# guac_v1.net
KiCad netlist of a schematic drawn in EAGLE
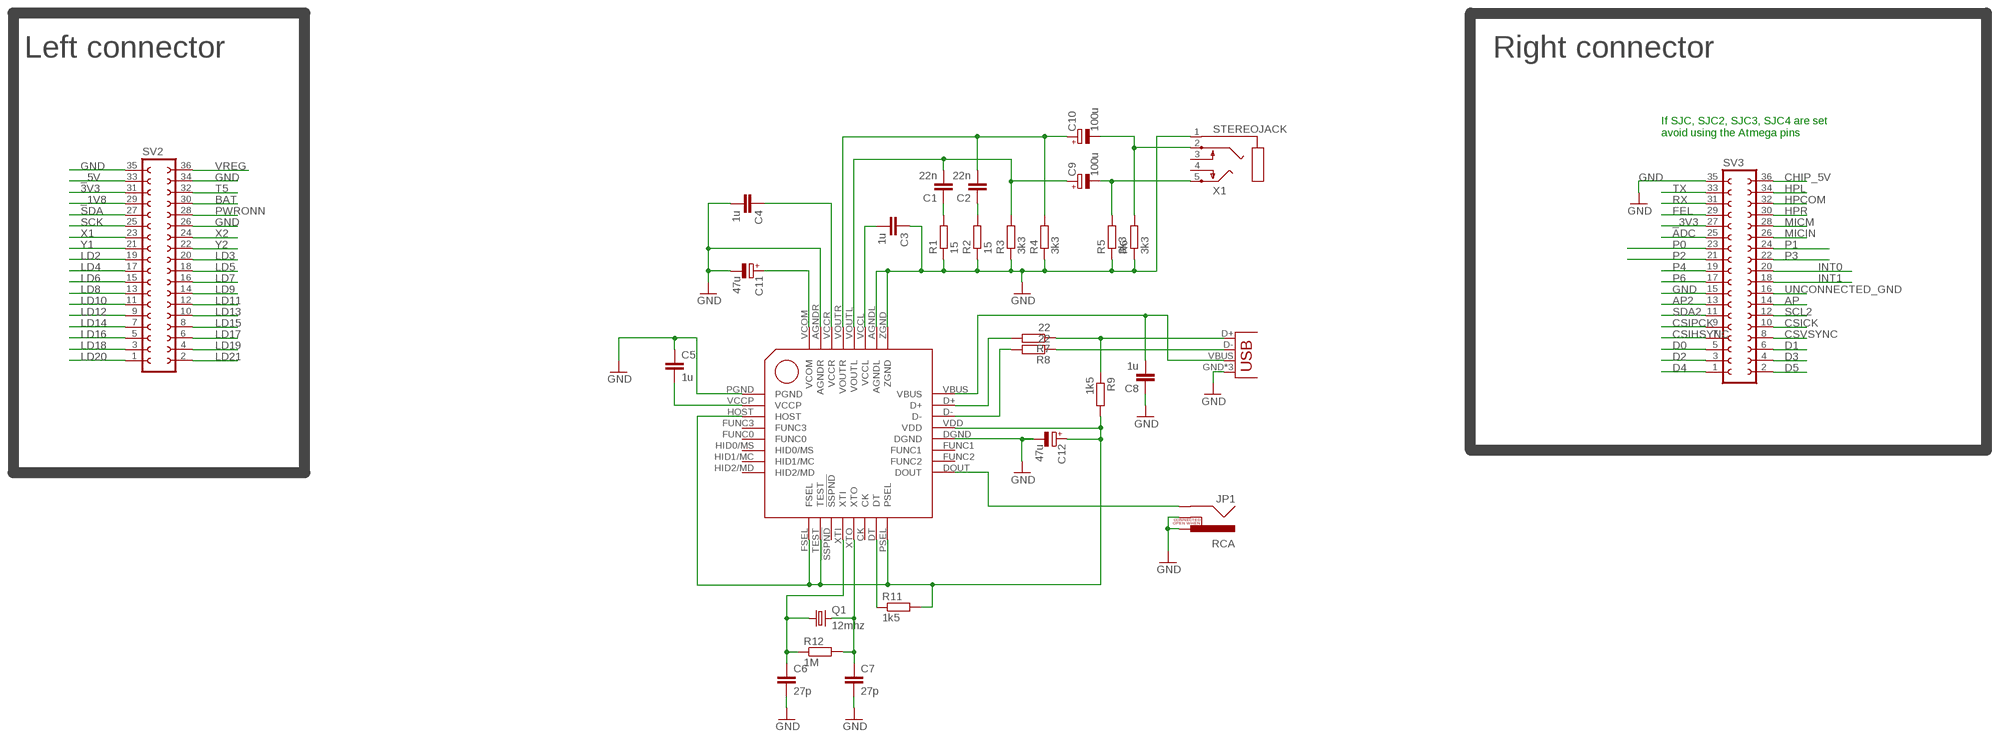
[diagram p0: schematic, sheet 1]

(export (version "E")
  (design (tool "Eeschema 10.0.6"))
  (components
    (comp (ref "C1")
      (value "22n")
      (footprint "eagle-import:C0805")
      (libsource (lib "eagle-import") (part "C-EUC0805"))
    )
    (comp (ref "C2")
      (value "22n")
      (footprint "eagle-import:C0805")
      (libsource (lib "eagle-import") (part "C-EUC0805"))
    )
    (comp (ref "C3")
      (value "1u")
      (footprint "eagle-import:C0805")
      (libsource (lib "eagle-import") (part "C-EUC0805"))
    )
    (comp (ref "C4")
      (value "1u")
      (footprint "eagle-import:C0805")
      (libsource (lib "eagle-import") (part "C-EUC0805"))
    )
    (comp (ref "C5")
      (value "1u")
      (footprint "eagle-import:C0805")
      (libsource (lib "eagle-import") (part "C-EUC0805"))
    )
    (comp (ref "C6")
      (value "27p")
      (footprint "eagle-import:C0805")
      (libsource (lib "eagle-import") (part "C-EUC0805"))
    )
    (comp (ref "C7")
      (value "27p")
      (footprint "eagle-import:C0805")
      (libsource (lib "eagle-import") (part "C-EUC0805"))
    )
    (comp (ref "C8")
      (value "1u")
      (footprint "eagle-import:C0805")
      (libsource (lib "eagle-import") (part "C-EUC0805"))
    )
    (comp (ref "C9")
      (value "100u")
      (footprint "eagle-import:140CLH-0810")
      (libsource (lib "eagle-import") (part "CPOL-EU140CLH-0810"))
    )
    (comp (ref "C10")
      (value "100u")
      (footprint "eagle-import:140CLH-0810")
      (libsource (lib "eagle-import") (part "CPOL-EU140CLH-0810"))
    )
    (comp (ref "C11")
      (value "47u")
      (footprint "eagle-import:140CLH-0810")
      (libsource (lib "eagle-import") (part "CPOL-EU140CLH-0810"))
    )
    (comp (ref "C12")
      (value "47u")
      (footprint "eagle-import:140CLH-0810")
      (libsource (lib "eagle-import") (part "CPOL-EU140CLH-0810"))
    )
    (comp (ref "JP1")
      (value "RCA")
      (footprint "eagle-import:RCA")
      (libsource (lib "eagle-import") (part "RCA"))
    )
    (comp (ref "Q1")
      (value "12mhz")
      (footprint "eagle-import:HC49UP")
      (libsource (lib "eagle-import") (part "CRYSTALHC49UP"))
    )
    (comp (ref "R1")
      (value "15")
      (footprint "eagle-import:M0805")
      (libsource (lib "eagle-import") (part "R-EU_M0805"))
    )
    (comp (ref "R2")
      (value "15")
      (footprint "eagle-import:M0805")
      (libsource (lib "eagle-import") (part "R-EU_M0805"))
    )
    (comp (ref "R3")
      (value "3k3")
      (footprint "eagle-import:M0805")
      (libsource (lib "eagle-import") (part "R-EU_M0805"))
    )
    (comp (ref "R4")
      (value "3k3")
      (footprint "eagle-import:M0805")
      (libsource (lib "eagle-import") (part "R-EU_M0805"))
    )
    (comp (ref "R5")
      (value "3k3")
      (footprint "eagle-import:M0805")
      (libsource (lib "eagle-import") (part "R-EU_M0805"))
    )
    (comp (ref "R6")
      (value "3k3")
      (footprint "eagle-import:M0805")
      (libsource (lib "eagle-import") (part "R-EU_M0805"))
    )
    (comp (ref "R7")
      (value "22")
      (footprint "eagle-import:M0805")
      (libsource (lib "eagle-import") (part "R-EU_M0805"))
    )
    (comp (ref "R8")
      (value "22")
      (footprint "eagle-import:M0805")
      (libsource (lib "eagle-import") (part "R-EU_M0805"))
    )
    (comp (ref "R9")
      (value "1k5")
      (footprint "eagle-import:M0805")
      (libsource (lib "eagle-import") (part "R-EU_M0805"))
    )
    (comp (ref "R11")
      (value "1k5")
      (footprint "eagle-import:M0805")
      (libsource (lib "eagle-import") (part "R-EU_M0805"))
    )
    (comp (ref "R12")
      (value "1M")
      (footprint "eagle-import:M0805")
      (libsource (lib "eagle-import") (part "R-EU_M0805"))
    )
    (comp (ref "SV2")
      (value "FE18-2")
      (footprint "eagle-import:FE18-2")
      (libsource (lib "eagle-import") (part "FE18-2"))
    )
    (comp (ref "SV3")
      (value "FE18-2")
      (footprint "eagle-import:FE18-2")
      (libsource (lib "eagle-import") (part "FE18-2"))
    )
    (comp (ref "U$1")
      (value "PCM2706")
      (footprint "eagle-import:TQFP32-08")
      (libsource (lib "eagle-import") (part "PCM2706"))
    )
    (comp (ref "USB")
      (value "USBUSB-MICROB-SMT-DIP")
      (footprint "eagle-import:USB-MICROB-SMT-DIP")
      (libsource (lib "eagle-import") (part "USBUSB-MICROB-SMT-DIP"))
    )
    (comp (ref "X1")
      (value "STEREOJACK")
      (footprint "eagle-import:STX3100")
      (libsource (lib "eagle-import") (part "STEREOJACK"))
    )
  )
  (nets
    (net (code "1") (name "/3V3") (class "Default")
      (node (ref "SV2") (pin "31") (pinfunction "31_31") (pintype "passive"))
    )
    (net (code "2") (name "/ADC") (class "Default")
      (node (ref "SV3") (pin "25") (pinfunction "25_25") (pintype "passive"))
    )
    (net (code "3") (name "/AP") (class "Default")
      (node (ref "SV3") (pin "14") (pinfunction "14_14") (pintype "passive"))
    )
    (net (code "4") (name "/AP2") (class "Default")
      (node (ref "SV3") (pin "13") (pinfunction "13_13") (pintype "passive"))
    )
    (net (code "5") (name "/BAT") (class "Default")
      (node (ref "SV2") (pin "30") (pinfunction "30_30") (pintype "passive"))
    )
    (net (code "6") (name "/CHIP_5V") (class "Default")
      (node (ref "SV3") (pin "36") (pinfunction "36_36") (pintype "passive"))
    )
    (net (code "7") (name "/CSICK") (class "Default")
      (node (ref "SV3") (pin "10") (pinfunction "10_10") (pintype "passive"))
    )
    (net (code "8") (name "/CSIHSYNC") (class "Default")
      (node (ref "SV3") (pin "7") (pinfunction "7_7") (pintype "passive"))
    )
    (net (code "9") (name "/CSIPCK") (class "Default")
      (node (ref "SV3") (pin "9") (pinfunction "9_9") (pintype "passive"))
    )
    (net (code "10") (name "/CSVSYNC") (class "Default")
      (node (ref "SV3") (pin "8") (pinfunction "8_8") (pintype "passive"))
    )
    (net (code "11") (name "/D0") (class "Default")
      (node (ref "SV3") (pin "5") (pinfunction "5_5") (pintype "passive"))
    )
    (net (code "12") (name "/D1") (class "Default")
      (node (ref "SV3") (pin "6") (pinfunction "6_6") (pintype "passive"))
    )
    (net (code "13") (name "/D2") (class "Default")
      (node (ref "SV3") (pin "3") (pinfunction "3_3") (pintype "passive"))
    )
    (net (code "14") (name "/D3") (class "Default")
      (node (ref "SV3") (pin "4") (pinfunction "4_4") (pintype "passive"))
    )
    (net (code "15") (name "/D4") (class "Default")
      (node (ref "SV3") (pin "1") (pinfunction "1_1") (pintype "passive"))
    )
    (net (code "16") (name "/D5") (class "Default")
      (node (ref "SV3") (pin "2") (pinfunction "2_2") (pintype "passive"))
    )
    (net (code "17") (name "/FEL") (class "Default")
      (node (ref "SV3") (pin "29") (pinfunction "29_29") (pintype "passive"))
    )
    (net (code "18") (name "/HPCOM") (class "Default")
      (node (ref "SV3") (pin "32") (pinfunction "32_32") (pintype "passive"))
    )
    (net (code "19") (name "/HPL") (class "Default")
      (node (ref "SV3") (pin "34") (pinfunction "34_34") (pintype "passive"))
    )
    (net (code "20") (name "/HPR") (class "Default")
      (node (ref "SV3") (pin "30") (pinfunction "30_30") (pintype "passive"))
    )
    (net (code "21") (name "/INT0") (class "Default")
      (node (ref "SV3") (pin "20") (pinfunction "20_20") (pintype "passive"))
    )
    (net (code "22") (name "/INT1") (class "Default")
      (node (ref "SV3") (pin "18") (pinfunction "18_18") (pintype "passive"))
    )
    (net (code "23") (name "/LD2") (class "Default")
      (node (ref "SV2") (pin "19") (pinfunction "19_19") (pintype "passive"))
    )
    (net (code "24") (name "/LD3") (class "Default")
      (node (ref "SV2") (pin "20") (pinfunction "20_20") (pintype "passive"))
    )
    (net (code "25") (name "/LD4") (class "Default")
      (node (ref "SV2") (pin "17") (pinfunction "17_17") (pintype "passive"))
    )
    (net (code "26") (name "/LD5") (class "Default")
      (node (ref "SV2") (pin "18") (pinfunction "18_18") (pintype "passive"))
    )
    (net (code "27") (name "/LD6") (class "Default")
      (node (ref "SV2") (pin "15") (pinfunction "15_15") (pintype "passive"))
    )
    (net (code "28") (name "/LD7") (class "Default")
      (node (ref "SV2") (pin "16") (pinfunction "16_16") (pintype "passive"))
    )
    (net (code "29") (name "/LD8") (class "Default")
      (node (ref "SV2") (pin "13") (pinfunction "13_13") (pintype "passive"))
    )
    (net (code "30") (name "/LD9") (class "Default")
      (node (ref "SV2") (pin "14") (pinfunction "14_14") (pintype "passive"))
    )
    (net (code "31") (name "/LD10") (class "Default")
      (node (ref "SV2") (pin "11") (pinfunction "11_11") (pintype "passive"))
    )
    (net (code "32") (name "/LD11") (class "Default")
      (node (ref "SV2") (pin "12") (pinfunction "12_12") (pintype "passive"))
    )
    (net (code "33") (name "/LD12") (class "Default")
      (node (ref "SV2") (pin "9") (pinfunction "9_9") (pintype "passive"))
    )
    (net (code "34") (name "/LD13") (class "Default")
      (node (ref "SV2") (pin "10") (pinfunction "10_10") (pintype "passive"))
    )
    (net (code "35") (name "/LD14") (class "Default")
      (node (ref "SV2") (pin "7") (pinfunction "7_7") (pintype "passive"))
    )
    (net (code "36") (name "/LD15") (class "Default")
      (node (ref "SV2") (pin "8") (pinfunction "8_8") (pintype "passive"))
    )
    (net (code "37") (name "/LD16") (class "Default")
      (node (ref "SV2") (pin "5") (pinfunction "5_5") (pintype "passive"))
    )
    (net (code "38") (name "/LD17") (class "Default")
      (node (ref "SV2") (pin "6") (pinfunction "6_6") (pintype "passive"))
    )
    (net (code "39") (name "/LD18") (class "Default")
      (node (ref "SV2") (pin "3") (pinfunction "3_3") (pintype "passive"))
    )
    (net (code "40") (name "/LD19") (class "Default")
      (node (ref "SV2") (pin "4") (pinfunction "4_4") (pintype "passive"))
    )
    (net (code "41") (name "/LD20") (class "Default")
      (node (ref "SV2") (pin "1") (pinfunction "1_1") (pintype "passive"))
    )
    (net (code "42") (name "/LD21") (class "Default")
      (node (ref "SV2") (pin "2") (pinfunction "2_2") (pintype "passive"))
    )
    (net (code "43") (name "/MICIN") (class "Default")
      (node (ref "SV3") (pin "26") (pinfunction "26_26") (pintype "passive"))
    )
    (net (code "44") (name "/MICM") (class "Default")
      (node (ref "SV3") (pin "28") (pinfunction "28_28") (pintype "passive"))
    )
    (net (code "45") (name "/P0") (class "Default")
      (node (ref "SV3") (pin "23") (pinfunction "23_23") (pintype "passive"))
    )
    (net (code "46") (name "/P1") (class "Default")
      (node (ref "SV3") (pin "24") (pinfunction "24_24") (pintype "passive"))
    )
    (net (code "47") (name "/P2") (class "Default")
      (node (ref "SV3") (pin "21") (pinfunction "21_21") (pintype "passive"))
    )
    (net (code "48") (name "/P3") (class "Default")
      (node (ref "SV3") (pin "22") (pinfunction "22_22") (pintype "passive"))
    )
    (net (code "49") (name "/P4") (class "Default")
      (node (ref "SV3") (pin "19") (pinfunction "19_19") (pintype "passive"))
    )
    (net (code "50") (name "/P6") (class "Default")
      (node (ref "SV3") (pin "17") (pinfunction "17_17") (pintype "passive"))
    )
    (net (code "51") (name "/PWRONN") (class "Default")
      (node (ref "SV2") (pin "28") (pinfunction "28_28") (pintype "passive"))
    )
    (net (code "52") (name "/RX") (class "Default")
      (node (ref "SV3") (pin "31") (pinfunction "31_31") (pintype "passive"))
    )
    (net (code "53") (name "/SCK") (class "Default")
      (node (ref "SV2") (pin "25") (pinfunction "25_25") (pintype "passive"))
    )
    (net (code "54") (name "/SCL2") (class "Default")
      (node (ref "SV3") (pin "12") (pinfunction "12_12") (pintype "passive"))
    )
    (net (code "55") (name "/SDA") (class "Default")
      (node (ref "SV2") (pin "27") (pinfunction "27_27") (pintype "passive"))
    )
    (net (code "56") (name "/SDA2") (class "Default")
      (node (ref "SV3") (pin "11") (pinfunction "11_11") (pintype "passive"))
    )
    (net (code "57") (name "/T5") (class "Default")
      (node (ref "SV2") (pin "32") (pinfunction "32_32") (pintype "passive"))
    )
    (net (code "58") (name "/TX") (class "Default")
      (node (ref "SV3") (pin "33") (pinfunction "33_33") (pintype "passive"))
    )
    (net (code "59") (name "/UNCONNECTED_GND") (class "Default")
      (node (ref "SV3") (pin "16") (pinfunction "16_16") (pintype "passive"))
    )
    (net (code "60") (name "/VREG") (class "Default")
      (node (ref "SV2") (pin "36") (pinfunction "36_36") (pintype "passive"))
    )
    (net (code "61") (name "/X1") (class "Default")
      (node (ref "SV2") (pin "23") (pinfunction "23_23") (pintype "passive"))
    )
    (net (code "62") (name "/X2") (class "Default")
      (node (ref "SV2") (pin "24") (pinfunction "24_24") (pintype "passive"))
    )
    (net (code "63") (name "/Y1") (class "Default")
      (node (ref "SV2") (pin "21") (pinfunction "21_21") (pintype "passive"))
    )
    (net (code "64") (name "/Y2") (class "Default")
      (node (ref "SV2") (pin "22") (pinfunction "22_22") (pintype "passive"))
    )
    (net (code "65") (name "/_1V8") (class "Default")
      (node (ref "SV2") (pin "29") (pinfunction "29_29") (pintype "passive"))
    )
    (net (code "66") (name "/_3V3") (class "Default")
      (node (ref "SV3") (pin "27") (pinfunction "27_27") (pintype "passive"))
    )
    (net (code "67") (name "/_5V") (class "Default")
      (node (ref "SV2") (pin "33") (pinfunction "33_33") (pintype "passive"))
    )
    (net (code "68") (name "GND") (class "Default")
      (node (ref "C11") (pin "-") (pinfunction "-_-") (pintype "passive"))
      (node (ref "C12") (pin "-") (pinfunction "-_-") (pintype "passive"))
      (node (ref "C3") (pin "1") (pinfunction "1_1") (pintype "passive"))
      (node (ref "C4") (pin "2") (pinfunction "2_2") (pintype "passive"))
      (node (ref "C5") (pin "1") (pinfunction "1_1") (pintype "passive"))
      (node (ref "C6") (pin "2") (pinfunction "2_2") (pintype "passive"))
      (node (ref "C7") (pin "2") (pinfunction "2_2") (pintype "passive"))
      (node (ref "C8") (pin "1") (pinfunction "1_1") (pintype "passive"))
      (node (ref "JP1") (pin "PIN") (pinfunction "PIN_PIN") (pintype "bidirectional"))
      (node (ref "JP1") (pin "SWITCH") (pinfunction "SWITCH_SWITCH") (pintype "bidirectional"))
      (node (ref "R1") (pin "1") (pinfunction "1_1") (pintype "passive"))
      (node (ref "R2") (pin "1") (pinfunction "1_1") (pintype "passive"))
      (node (ref "R3") (pin "1") (pinfunction "1_1") (pintype "passive"))
      (node (ref "R4") (pin "1") (pinfunction "1_1") (pintype "passive"))
      (node (ref "R5") (pin "1") (pinfunction "1_1") (pintype "passive"))
      (node (ref "R6") (pin "1") (pinfunction "1_1") (pintype "passive"))
      (node (ref "SV2") (pin "26") (pinfunction "26_26") (pintype "passive"))
      (node (ref "SV2") (pin "34") (pinfunction "34_34") (pintype "passive"))
      (node (ref "SV2") (pin "35") (pinfunction "35_35") (pintype "passive"))
      (node (ref "SV3") (pin "15") (pinfunction "15_15") (pintype "passive"))
      (node (ref "SV3") (pin "35") (pinfunction "35_35") (pintype "passive"))
      (node (ref "U$1") (pin "AGNDL") (pinfunction "AGNDL_AGNDL") (pintype "power_in"))
      (node (ref "U$1") (pin "AGNDR") (pinfunction "AGNDR_AGNDR") (pintype "power_in"))
      (node (ref "U$1") (pin "DGND") (pinfunction "DGND_DGND") (pintype "power_in"))
      (node (ref "U$1") (pin "PGND") (pinfunction "PGND_PGND") (pintype "power_in"))
      (node (ref "U$1") (pin "ZGND") (pinfunction "ZGND_ZGND") (pintype "power_in"))
      (node (ref "USB") (pin "GND") (pinfunction "GND_GND") (pintype "bidirectional"))
      (node (ref "USB") (pin "MT1") (pinfunction "GND_MT1") (pintype "bidirectional"))
      (node (ref "USB") (pin "MT2") (pinfunction "GND_MT2") (pintype "bidirectional"))
      (node (ref "X1") (pin "1") (pinfunction "1_1") (pintype "passive"))
    )
    (net (code "69") (name "Net-(C1-Pad1)") (class "Default")
      (node (ref "C1") (pin "1") (pinfunction "1_1") (pintype "passive"))
      (node (ref "R1") (pin "2") (pinfunction "2_2") (pintype "passive"))
    )
    (net (code "70") (name "Net-(C1-Pad2)") (class "Default")
      (node (ref "C1") (pin "2") (pinfunction "2_2") (pintype "passive"))
      (node (ref "C9") (pin "+") (pinfunction "+_+") (pintype "passive"))
      (node (ref "R3") (pin "2") (pinfunction "2_2") (pintype "passive"))
      (node (ref "U$1") (pin "VOUTL") (pinfunction "VOUTL_VOUTL") (pintype "output"))
    )
    (net (code "71") (name "Net-(C2-Pad1)") (class "Default")
      (node (ref "C2") (pin "1") (pinfunction "1_1") (pintype "passive"))
      (node (ref "R2") (pin "2") (pinfunction "2_2") (pintype "passive"))
    )
    (net (code "72") (name "Net-(C3-Pad2)") (class "Default")
      (node (ref "C3") (pin "2") (pinfunction "2_2") (pintype "passive"))
      (node (ref "U$1") (pin "VCCL") (pinfunction "VCCL_VCCL") (pintype "power_in"))
    )
    (net (code "73") (name "Net-(C4-Pad1)") (class "Default")
      (node (ref "C4") (pin "1") (pinfunction "1_1") (pintype "passive"))
      (node (ref "U$1") (pin "VCCR") (pinfunction "VCCR_VCCR") (pintype "power_in"))
    )
    (net (code "74") (name "Net-(C5-Pad2)") (class "Default")
      (node (ref "C5") (pin "2") (pinfunction "2_2") (pintype "passive"))
      (node (ref "U$1") (pin "VCCP") (pinfunction "VCCP_VCCP") (pintype "power_in"))
    )
    (net (code "75") (name "Net-(C6-Pad1)") (class "Default")
      (node (ref "C6") (pin "1") (pinfunction "1_1") (pintype "passive"))
      (node (ref "Q1") (pin "1") (pinfunction "1_1") (pintype "passive"))
      (node (ref "R12") (pin "1") (pinfunction "1_1") (pintype "passive"))
      (node (ref "U$1") (pin "XTI") (pinfunction "XTI_XTI") (pintype "bidirectional"))
    )
    (net (code "76") (name "Net-(C7-Pad1)") (class "Default")
      (node (ref "C7") (pin "1") (pinfunction "1_1") (pintype "passive"))
      (node (ref "Q1") (pin "2") (pinfunction "2_2") (pintype "passive"))
      (node (ref "R12") (pin "2") (pinfunction "2_2") (pintype "passive"))
      (node (ref "U$1") (pin "XTO") (pinfunction "XTO_XTO") (pintype "bidirectional"))
    )
    (net (code "77") (name "Net-(C8-Pad2)") (class "Default")
      (node (ref "C8") (pin "2") (pinfunction "2_2") (pintype "passive"))
      (node (ref "U$1") (pin "VBUS") (pinfunction "VBUS_VBUS") (pintype "power_in"))
      (node (ref "USB") (pin "VBUS") (pinfunction "VBUS_VBUS") (pintype "bidirectional"))
    )
    (net (code "78") (name "Net-(C9-Pad-)") (class "Default")
      (node (ref "C9") (pin "-") (pinfunction "-_-") (pintype "passive"))
      (node (ref "R5") (pin "2") (pinfunction "2_2") (pintype "passive"))
      (node (ref "X1") (pin "5") (pinfunction "5_5") (pintype "passive"))
    )
    (net (code "79") (name "Net-(C10-Pad+)") (class "Default")
      (node (ref "C10") (pin "+") (pinfunction "+_+") (pintype "passive"))
      (node (ref "C2") (pin "2") (pinfunction "2_2") (pintype "passive"))
      (node (ref "R4") (pin "2") (pinfunction "2_2") (pintype "passive"))
      (node (ref "U$1") (pin "VOUTR") (pinfunction "VOUTR_VOUTR") (pintype "output"))
    )
    (net (code "80") (name "Net-(C10-Pad-)") (class "Default")
      (node (ref "C10") (pin "-") (pinfunction "-_-") (pintype "passive"))
      (node (ref "R6") (pin "2") (pinfunction "2_2") (pintype "passive"))
      (node (ref "X1") (pin "2") (pinfunction "2_2") (pintype "passive"))
    )
    (net (code "81") (name "Net-(C11-Pad+)") (class "Default")
      (node (ref "C11") (pin "+") (pinfunction "+_+") (pintype "passive"))
      (node (ref "U$1") (pin "VCOM") (pinfunction "VCOM_VCOM") (pintype "power_in"))
    )
    (net (code "82") (name "Net-(C12-Pad+)") (class "Default")
      (node (ref "C12") (pin "+") (pinfunction "+_+") (pintype "passive"))
      (node (ref "R11") (pin "2") (pinfunction "2_2") (pintype "passive"))
      (node (ref "R9") (pin "2") (pinfunction "2_2") (pintype "passive"))
      (node (ref "U$1") (pin "FSEL") (pinfunction "FSEL_FSEL") (pintype "bidirectional"))
      (node (ref "U$1") (pin "HOST") (pinfunction "HOST_HOST") (pintype "power_in"))
      (node (ref "U$1") (pin "PSEL") (pinfunction "PSEL_PSEL") (pintype "bidirectional"))
      (node (ref "U$1") (pin "TEST") (pinfunction "TEST_TEST") (pintype "bidirectional"))
      (node (ref "U$1") (pin "VDD") (pinfunction "VDD_VDD") (pintype "power_in"))
    )
    (net (code "83") (name "Net-(JP1-PadSHELL)") (class "Default")
      (node (ref "JP1") (pin "SHELL") (pinfunction "SHELL_SHELL") (pintype "bidirectional"))
      (node (ref "U$1") (pin "DOUT") (pinfunction "DOUT_DOUT") (pintype "bidirectional"))
    )
    (net (code "84") (name "Net-(R7-Pad1)") (class "Default")
      (node (ref "R7") (pin "1") (pinfunction "1_1") (pintype "passive"))
      (node (ref "R9") (pin "1") (pinfunction "1_1") (pintype "passive"))
      (node (ref "USB") (pin "D+") (pinfunction "D+_D+") (pintype "bidirectional"))
    )
    (net (code "85") (name "Net-(R7-Pad2)") (class "Default")
      (node (ref "R7") (pin "2") (pinfunction "2_2") (pintype "passive"))
      (node (ref "U$1") (pin "D+") (pinfunction "D+_D+") (pintype "bidirectional"))
    )
    (net (code "86") (name "Net-(R8-Pad1)") (class "Default")
      (node (ref "R8") (pin "1") (pinfunction "1_1") (pintype "passive"))
      (node (ref "USB") (pin "D-") (pinfunction "D-_D-") (pintype "bidirectional"))
    )
    (net (code "87") (name "Net-(R8-Pad2)") (class "Default")
      (node (ref "R8") (pin "2") (pinfunction "2_2") (pintype "passive"))
      (node (ref "U$1") (pin "D-") (pinfunction "D-_D-") (pintype "bidirectional"))
    )
    (net (code "88") (name "Net-(R11-Pad1)") (class "Default")
      (node (ref "R11") (pin "1") (pinfunction "1_1") (pintype "passive"))
      (node (ref "U$1") (pin "DT") (pinfunction "DT_DT") (pintype "bidirectional"))
    )
    (net (code "89") (name "unconnected-(U$1-PadCK)") (class "Default")
      (node (ref "U$1") (pin "CK") (pinfunction "CK_CK") (pintype "bidirectional"))
    )
    (net (code "90") (name "unconnected-(U$1-PadFUNC0)") (class "Default")
      (node (ref "U$1") (pin "FUNC0") (pinfunction "FUNC0_FUNC0") (pintype "bidirectional"))
    )
    (net (code "91") (name "unconnected-(U$1-PadFUNC1)") (class "Default")
      (node (ref "U$1") (pin "FUNC1") (pinfunction "FUNC1_FUNC1") (pintype "bidirectional"))
    )
    (net (code "92") (name "unconnected-(U$1-PadFUNC2)") (class "Default")
      (node (ref "U$1") (pin "FUNC2") (pinfunction "FUNC2_FUNC2") (pintype "bidirectional"))
    )
    (net (code "93") (name "unconnected-(U$1-PadFUNC3)") (class "Default")
      (node (ref "U$1") (pin "FUNC3") (pinfunction "FUNC3_FUNC3") (pintype "bidirectional"))
    )
    (net (code "94") (name "unconnected-(U$1-PadHID0{slash}MS)") (class "Default")
      (node (ref "U$1") (pin "HID0/MS") (pinfunction "HID0/MS_HID0/MS") (pintype "bidirectional"))
    )
    (net (code "95") (name "unconnected-(U$1-PadHID1{slash}MC)") (class "Default")
      (node (ref "U$1") (pin "HID1/MC") (pinfunction "HID1/MC_HID1/MC") (pintype "bidirectional"))
    )
    (net (code "96") (name "unconnected-(U$1-PadHID2{slash}MD)") (class "Default")
      (node (ref "U$1") (pin "HID2/MD") (pinfunction "HID2/MD_HID2/MD") (pintype "bidirectional"))
    )
    (net (code "97") (name "unconnected-(U$1-~{SSPND}-Pad!SSPND)") (class "Default")
      (node (ref "U$1") (pin "!SSPND") (pinfunction "~{SSPND}_!SSPND") (pintype "bidirectional"))
    )
    (net (code "98") (name "unconnected-(X1-Pad3)") (class "Default")
      (node (ref "X1") (pin "3") (pinfunction "3_3") (pintype "passive"))
    )
    (net (code "99") (name "unconnected-(X1-Pad4)") (class "Default")
      (node (ref "X1") (pin "4") (pinfunction "4_4") (pintype "passive"))
    )
  )
)
